# StepperMotorController.net
KiCad netlist of a schematic drawn in Altium Designer
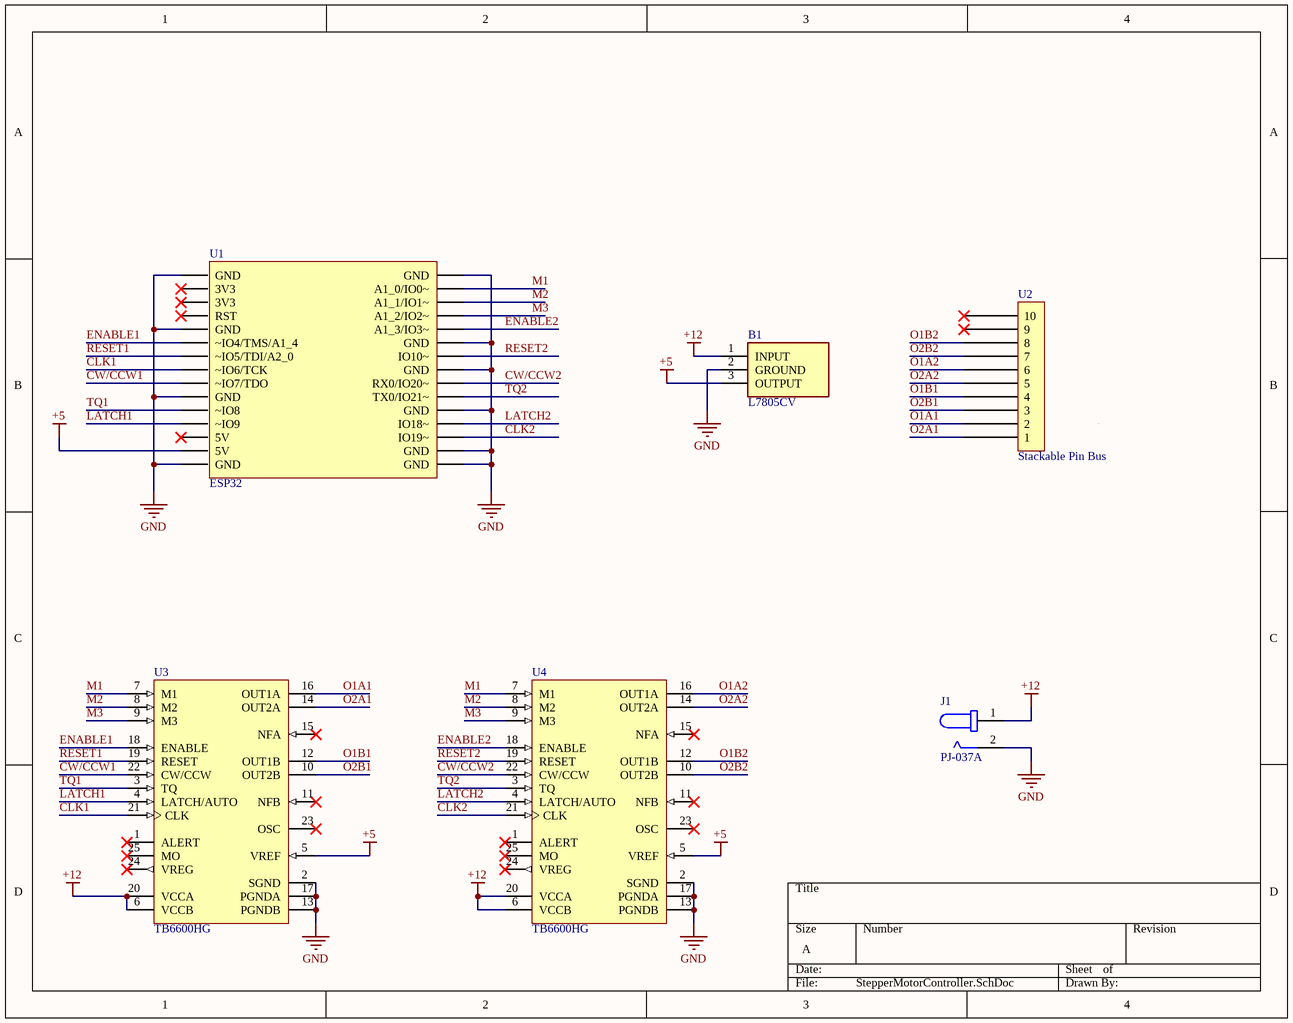
[diagram p0: StepperMotorController.SchDoc]

(export (version "E")
  (design (tool "Eeschema 10.0.6"))
  (components
    (comp (ref "B1")
      (value "L7805CV")
      (footprint "TO255P460X1020X2008-3P")
      (fields (field (name "MOUSER PART NUMBER") "511-L7805CV"))
      (libsource (lib "StepperMotorController") (part "L7805CV"))
    )
    (comp (ref "J1")
      (value "PJ-037A")
      (footprint "CUI_PJ-037A")
      (description "2.0 mm Center Pin, 2.5 A, Right Angle, Through Hole, Dc Power Jack Connector")
      (libsource (lib "StepperMotorController") (part "PJ-037A"))
    )
    (comp (ref "U1")
      (value "ESP32")
      (footprint "ESP32")
      (fields
        (field (name "MANUFACTURER") "Espressif Systems")
        (field (name "MANUFACTURER PART NUMBER") "ESP32-C3-DEVKITC-02")
      )
      (libsource (lib "StepperMotorController") (part "ESP32-C3-DEVKITC-02"))
    )
    (comp (ref "U2")
      (value "Stackable Pin Bus")
      (footprint "STACKABLE_PIN_BUS")
      (description "10 pinos, Passo 2.54mm, Dimensões da barra 26x2x8mm")
      (libsource (lib "StepperMotorController") (part "Barramento Empilhável"))
    )
    (comp (ref "U3")
      (value "TB6600HG")
      (footprint "TOSH-HZIP25-1.00F-25")
      (fields (field (name "MANUFACTURER") "Toshiba"))
      (libsource (lib "StepperMotorController") (part "CMP-0695-00001-1"))
    )
    (comp (ref "U4")
      (value "TB6600HG")
      (footprint "TOSH-HZIP25-1.00F-25")
      (fields (field (name "MANUFACTURER") "Toshiba"))
      (libsource (lib "StepperMotorController") (part "TB550HD"))
    )
  )
  (nets
    (net (code "1") (name "+5") (class "Default")
      (node (ref "B1") (pin "3") (pinfunction "OUTPUT_3") (pintype "passive"))
      (node (ref "U1") (pin "14") (pinfunction "5V_14") (pintype "passive"))
      (node (ref "U3") (pin "5") (pinfunction "VREF_5") (pintype "input"))
      (node (ref "U4") (pin "5") (pinfunction "VREF_5") (pintype "input"))
    )
    (net (code "2") (name "+12") (class "Default")
      (node (ref "B1") (pin "1") (pinfunction "INPUT_1") (pintype "passive"))
      (node (ref "J1") (pin "1") (pinfunction "1_1") (pintype "passive"))
      (node (ref "U3") (pin "20") (pinfunction "VCCA_20") (pintype "power_in"))
      (node (ref "U3") (pin "6") (pinfunction "VCCB_6") (pintype "power_in"))
      (node (ref "U4") (pin "20") (pinfunction "VCCA_20") (pintype "power_in"))
      (node (ref "U4") (pin "6") (pinfunction "VCCB_6") (pintype "power_in"))
    )
    (net (code "3") (name "/CLK1") (class "Default")
      (node (ref "U1") (pin "8") (pinfunction "~IO6/TCK_8") (pintype "passive"))
      (node (ref "U3") (pin "21") (pinfunction "CLK_21") (pintype "input"))
    )
    (net (code "4") (name "/CLK2") (class "Default")
      (node (ref "U1") (pin "18") (pinfunction "IO19~_18") (pintype "passive"))
      (node (ref "U4") (pin "21") (pinfunction "CLK_21") (pintype "input"))
    )
    (net (code "5") (name "/CW{slash}CCW1") (class "Default")
      (node (ref "U1") (pin "9") (pinfunction "~IO7/TDO_9") (pintype "passive"))
      (node (ref "U3") (pin "22") (pinfunction "CW/CCW_22") (pintype "input"))
    )
    (net (code "6") (name "/CW{slash}CCW2") (class "Default")
      (node (ref "U1") (pin "22") (pinfunction "RX0/IO20~_22") (pintype "passive"))
      (node (ref "U4") (pin "22") (pinfunction "CW/CCW_22") (pintype "input"))
    )
    (net (code "7") (name "/ENABLE1") (class "Default")
      (node (ref "U1") (pin "6") (pinfunction "~IO4/TMS/A1_4_6") (pintype "passive"))
      (node (ref "U3") (pin "18") (pinfunction "ENABLE_18") (pintype "input"))
    )
    (net (code "8") (name "/ENABLE2") (class "Default")
      (node (ref "U1") (pin "26") (pinfunction "A1_3/IO3~_26") (pintype "passive"))
      (node (ref "U4") (pin "18") (pinfunction "ENABLE_18") (pintype "input"))
    )
    (net (code "9") (name "/LATCH1") (class "Default")
      (node (ref "U1") (pin "12") (pinfunction "~IO9_12") (pintype "passive"))
      (node (ref "U3") (pin "4") (pinfunction "LATCH/AUTO_4") (pintype "input"))
    )
    (net (code "10") (name "/LATCH2") (class "Default")
      (node (ref "U1") (pin "19") (pinfunction "IO18~_19") (pintype "passive"))
      (node (ref "U4") (pin "4") (pinfunction "LATCH/AUTO_4") (pintype "input"))
    )
    (net (code "11") (name "/M1") (class "Default")
      (node (ref "U1") (pin "29") (pinfunction "A1_0/IO0~_29") (pintype "passive"))
      (node (ref "U3") (pin "7") (pinfunction "M1_7") (pintype "input"))
      (node (ref "U4") (pin "7") (pinfunction "M1_7") (pintype "input"))
    )
    (net (code "12") (name "/M2") (class "Default")
      (node (ref "U1") (pin "28") (pinfunction "A1_1/IO1~_28") (pintype "passive"))
      (node (ref "U3") (pin "8") (pinfunction "M2_8") (pintype "input"))
      (node (ref "U4") (pin "8") (pinfunction "M2_8") (pintype "input"))
    )
    (net (code "13") (name "/M3") (class "Default")
      (node (ref "U1") (pin "27") (pinfunction "A1_2/IO2~_27") (pintype "passive"))
      (node (ref "U3") (pin "9") (pinfunction "M3_9") (pintype "input"))
      (node (ref "U4") (pin "9") (pinfunction "M3_9") (pintype "input"))
    )
    (net (code "14") (name "/O1A1") (class "Default")
      (node (ref "U2") (pin "2") (pinfunction "2_2") (pintype "passive"))
      (node (ref "U3") (pin "16") (pinfunction "OUT1A_16") (pintype "tri_state"))
    )
    (net (code "15") (name "/O1A2") (class "Default")
      (node (ref "U2") (pin "6") (pinfunction "6_6") (pintype "passive"))
      (node (ref "U4") (pin "16") (pinfunction "OUT1A_16") (pintype "tri_state"))
    )
    (net (code "16") (name "/O1B1") (class "Default")
      (node (ref "U2") (pin "4") (pinfunction "4_4") (pintype "passive"))
      (node (ref "U3") (pin "12") (pinfunction "OUT1B_12") (pintype "tri_state"))
    )
    (net (code "17") (name "/O1B2") (class "Default")
      (node (ref "U2") (pin "8") (pinfunction "8_8") (pintype "passive"))
      (node (ref "U4") (pin "12") (pinfunction "OUT1B_12") (pintype "tri_state"))
    )
    (net (code "18") (name "/O2A1") (class "Default")
      (node (ref "U2") (pin "1") (pinfunction "1_1") (pintype "passive"))
      (node (ref "U3") (pin "14") (pinfunction "OUT2A_14") (pintype "tri_state"))
    )
    (net (code "19") (name "/O2A2") (class "Default")
      (node (ref "U2") (pin "5") (pinfunction "5_5") (pintype "passive"))
      (node (ref "U4") (pin "14") (pinfunction "OUT2A_14") (pintype "tri_state"))
    )
    (net (code "20") (name "/O2B1") (class "Default")
      (node (ref "U2") (pin "3") (pinfunction "3_3") (pintype "passive"))
      (node (ref "U3") (pin "10") (pinfunction "OUT2B_10") (pintype "tri_state"))
    )
    (net (code "21") (name "/O2B2") (class "Default")
      (node (ref "U2") (pin "7") (pinfunction "7_7") (pintype "passive"))
      (node (ref "U4") (pin "10") (pinfunction "OUT2B_10") (pintype "tri_state"))
    )
    (net (code "22") (name "/RESET1") (class "Default")
      (node (ref "U1") (pin "7") (pinfunction "~IO5/TDI/A2_0_7") (pintype "passive"))
      (node (ref "U3") (pin "19") (pinfunction "RESET_19") (pintype "input"))
    )
    (net (code "23") (name "/RESET2") (class "Default")
      (node (ref "U1") (pin "24") (pinfunction "IO10~_24") (pintype "passive"))
      (node (ref "U4") (pin "19") (pinfunction "RESET_19") (pintype "input"))
    )
    (net (code "24") (name "/TQ1") (class "Default")
      (node (ref "U1") (pin "11") (pinfunction "~IO8_11") (pintype "passive"))
      (node (ref "U3") (pin "3") (pinfunction "TQ_3") (pintype "input"))
    )
    (net (code "25") (name "/TQ2") (class "Default")
      (node (ref "U1") (pin "21") (pinfunction "TX0/IO21~_21") (pintype "passive"))
      (node (ref "U4") (pin "3") (pinfunction "TQ_3") (pintype "input"))
    )
    (net (code "26") (name "GND") (class "Default")
      (node (ref "B1") (pin "2") (pinfunction "GROUND_2") (pintype "passive"))
      (node (ref "J1") (pin "2") (pinfunction "2_2") (pintype "passive"))
      (node (ref "U1") (pin "1") (pinfunction "GND_1") (pintype "passive"))
      (node (ref "U1") (pin "10") (pinfunction "GND_10") (pintype "passive"))
      (node (ref "U1") (pin "15") (pinfunction "GND_15") (pintype "passive"))
      (node (ref "U1") (pin "16") (pinfunction "GND_16") (pintype "passive"))
      (node (ref "U1") (pin "17") (pinfunction "GND_17") (pintype "passive"))
      (node (ref "U1") (pin "20") (pinfunction "GND_20") (pintype "passive"))
      (node (ref "U1") (pin "23") (pinfunction "GND_23") (pintype "passive"))
      (node (ref "U1") (pin "25") (pinfunction "GND_25") (pintype "passive"))
      (node (ref "U1") (pin "30") (pinfunction "GND_30") (pintype "passive"))
      (node (ref "U1") (pin "5") (pinfunction "GND_5") (pintype "passive"))
      (node (ref "U3") (pin "13") (pinfunction "PGNDB_13") (pintype "power_in"))
      (node (ref "U3") (pin "17") (pinfunction "PGNDA_17") (pintype "power_in"))
      (node (ref "U3") (pin "2") (pinfunction "SGND_2") (pintype "power_in"))
      (node (ref "U4") (pin "13") (pinfunction "PGNDB_13") (pintype "power_in"))
      (node (ref "U4") (pin "17") (pinfunction "PGNDA_17") (pintype "power_in"))
      (node (ref "U4") (pin "2") (pinfunction "SGND_2") (pintype "power_in"))
    )
    (net (code "27") (name "unconnected-(U1-3V3-Pad2)") (class "Default")
      (node (ref "U1") (pin "2") (pinfunction "3V3_2") (pintype "passive+no_connect"))
    )
    (net (code "28") (name "unconnected-(U1-3V3-Pad3)") (class "Default")
      (node (ref "U1") (pin "3") (pinfunction "3V3_3") (pintype "passive+no_connect"))
    )
    (net (code "29") (name "unconnected-(U1-5V-Pad13)") (class "Default")
      (node (ref "U1") (pin "13") (pinfunction "5V_13") (pintype "passive+no_connect"))
    )
    (net (code "30") (name "unconnected-(U1-RST-Pad4)") (class "Default")
      (node (ref "U1") (pin "4") (pinfunction "RST_4") (pintype "passive+no_connect"))
    )
    (net (code "31") (name "unconnected-(U2-Pad9)") (class "Default")
      (node (ref "U2") (pin "9") (pinfunction "9_9") (pintype "passive+no_connect"))
    )
    (net (code "32") (name "unconnected-(U2-Pad10)") (class "Default")
      (node (ref "U2") (pin "10") (pinfunction "10_10") (pintype "passive+no_connect"))
    )
    (net (code "33") (name "unconnected-(U3-ALERT-Pad1)") (class "Default")
      (node (ref "U3") (pin "1") (pinfunction "ALERT_1") (pintype "open_collector+no_connect"))
    )
    (net (code "34") (name "unconnected-(U3-MO-Pad25)") (class "Default")
      (node (ref "U3") (pin "25") (pinfunction "MO_25") (pintype "open_collector+no_connect"))
    )
    (net (code "35") (name "unconnected-(U3-NFA-Pad15)") (class "Default")
      (node (ref "U3") (pin "15") (pinfunction "NFA_15") (pintype "input+no_connect"))
    )
    (net (code "36") (name "unconnected-(U3-NFB-Pad11)") (class "Default")
      (node (ref "U3") (pin "11") (pinfunction "NFB_11") (pintype "input+no_connect"))
    )
    (net (code "37") (name "unconnected-(U3-OSC-Pad23)") (class "Default")
      (node (ref "U3") (pin "23") (pinfunction "OSC_23") (pintype "passive+no_connect"))
    )
    (net (code "38") (name "unconnected-(U3-VREG-Pad24)") (class "Default")
      (node (ref "U3") (pin "24") (pinfunction "VREG_24") (pintype "output+no_connect"))
    )
    (net (code "39") (name "unconnected-(U4-ALERT-Pad1)") (class "Default")
      (node (ref "U4") (pin "1") (pinfunction "ALERT_1") (pintype "open_collector+no_connect"))
    )
    (net (code "40") (name "unconnected-(U4-MO-Pad25)") (class "Default")
      (node (ref "U4") (pin "25") (pinfunction "MO_25") (pintype "open_collector+no_connect"))
    )
    (net (code "41") (name "unconnected-(U4-NFA-Pad15)") (class "Default")
      (node (ref "U4") (pin "15") (pinfunction "NFA_15") (pintype "input+no_connect"))
    )
    (net (code "42") (name "unconnected-(U4-NFB-Pad11)") (class "Default")
      (node (ref "U4") (pin "11") (pinfunction "NFB_11") (pintype "input+no_connect"))
    )
    (net (code "43") (name "unconnected-(U4-OSC-Pad23)") (class "Default")
      (node (ref "U4") (pin "23") (pinfunction "OSC_23") (pintype "passive+no_connect"))
    )
    (net (code "44") (name "unconnected-(U4-VREG-Pad24)") (class "Default")
      (node (ref "U4") (pin "24") (pinfunction "VREG_24") (pintype "output+no_connect"))
    )
  )
)
